# Power.net
KiCad netlist of a schematic drawn in Altium Designer
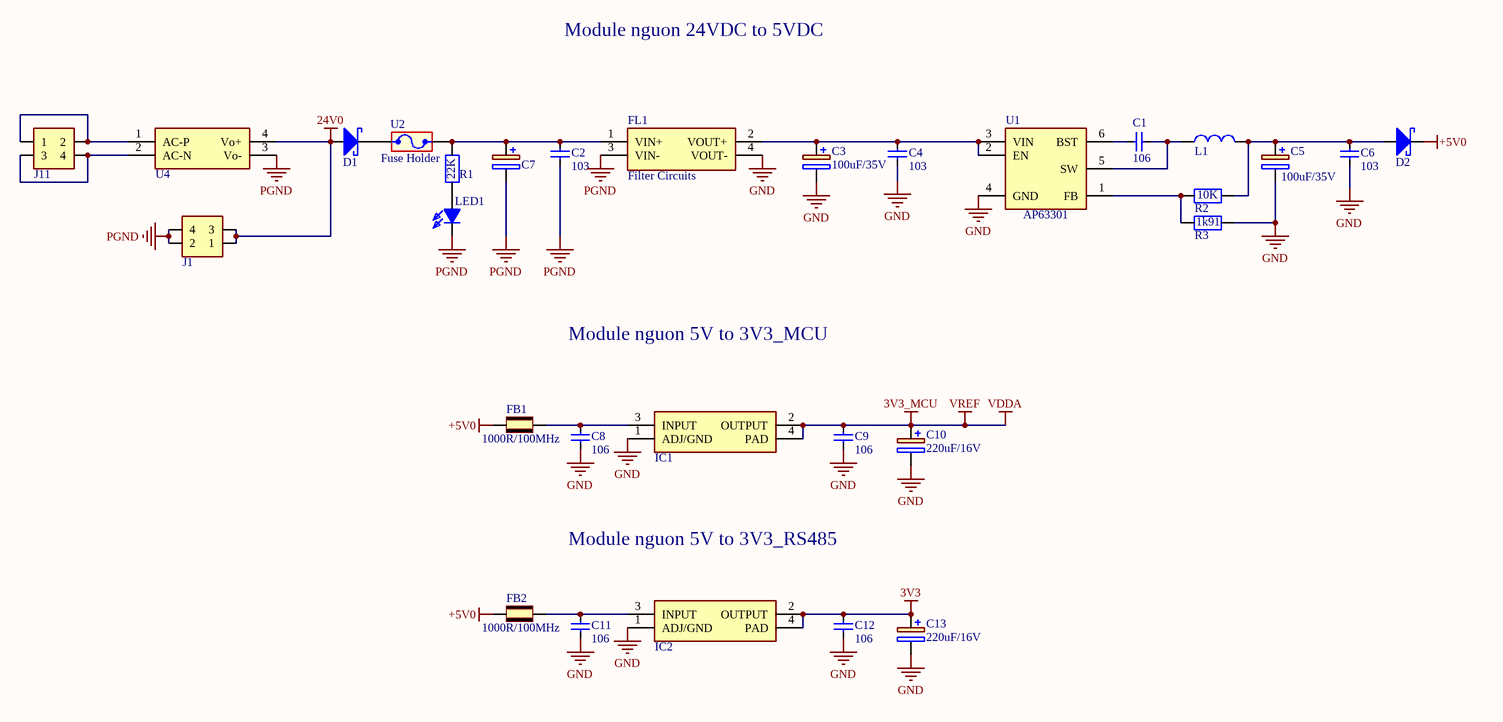
[diagram p0: Power.SchDoc]

(export (version "E")
  (design (tool "Eeschema 10.0.6"))
  (components
    (comp (ref "C1")
      (value "106")
      (footprint "SamacSys:CAPC1608X95N")
      (fields
        (field (name "MANUFACTURER_PART_NUMBER") "GRM188D71A106KA73D")
        (field (name "MOUSER PART NUMBER") "81-GRM188D71A106KA3D")
      )
      (libsource (lib "SamacSys") (part "Cap 106 - 0603"))
    )
    (comp (ref "C2")
      (value "103")
      (footprint "SamacSys:CAPC1608X95N")
      (fields
        (field (name "MANUFACTURER_PART_NUMBER") "CC0603KRX7R9BB103")
        (field (name "MOUSER PART NUMBER") "603-CC603KRX7R9BB103")
      )
      (libsource (lib "SamacSys") (part "Cap 103 - 0603"))
    )
    (comp (ref "C3")
      (value "100uF/35V")
      (footprint "SamacSys:CAPAE850X1050N")
      (description "Aluminium Electrolytic Capacitors - SMD 100UF 35V 105C 2500H")
      (fields
        (field (name "MANUFACTURER_PART_NUMBER") "MAL215097011E3")
        (field (name "MOUSER PART NUMBER") "594-MAL215097011E3")
      )
      (libsource (lib "SamacSys") (part "Cap smd 100uF/35V"))
    )
    (comp (ref "C4")
      (value "103")
      (footprint "SamacSys:CAPC1608X95N")
      (fields
        (field (name "MANUFACTURER_PART_NUMBER") "CC0603KRX7R9BB103")
        (field (name "MOUSER PART NUMBER") "603-CC603KRX7R9BB103")
      )
      (libsource (lib "SamacSys") (part "Cap 103 - 0603"))
    )
    (comp (ref "C5")
      (value "100uF/35V")
      (footprint "SamacSys:CAPAE850X1050N")
      (description "Aluminium Electrolytic Capacitors - SMD 100UF 35V 105C 2500H")
      (fields
        (field (name "MANUFACTURER_PART_NUMBER") "MAL215097011E3")
        (field (name "MOUSER PART NUMBER") "594-MAL215097011E3")
      )
      (libsource (lib "SamacSys") (part "Cap smd 100uF/35V"))
    )
    (comp (ref "C6")
      (value "103")
      (footprint "SamacSys:CAPC1608X95N")
      (fields
        (field (name "MANUFACTURER_PART_NUMBER") "CC0603KRX7R9BB103")
        (field (name "MOUSER PART NUMBER") "603-CC603KRX7R9BB103")
      )
      (libsource (lib "SamacSys") (part "Cap 103 - 0603"))
    )
    (comp (ref "C7")
      (value "330uF/35V")
      (footprint "SamacSys:CAPAE1000X1270N")
      (description "Aluminum Organic Polymer Capacitors 35Vol 330uF SMD 2KHr ESR=22 mOhms AECQ200")
      (fields
        (field (name "MANUFACTURER_PART_NUMBER") "A768MS337M1VLAS022")
        (field (name "MOUSER PART NUMBER") "80-A768MS337M1VLAS22")
      )
      (libsource (lib "SamacSys") (part "Cap smd 330uF/35V"))
    )
    (comp (ref "C8")
      (value "106")
      (footprint "SamacSys:CAPC1608X95N")
      (fields
        (field (name "MANUFACTURER_PART_NUMBER") "GRM188D71A106KA73D")
        (field (name "MOUSER PART NUMBER") "81-GRM188D71A106KA3D")
      )
      (libsource (lib "SamacSys") (part "Cap 106 - 0603"))
    )
    (comp (ref "C9")
      (value "106")
      (footprint "SamacSys:CAPC1608X95N")
      (fields
        (field (name "MANUFACTURER_PART_NUMBER") "GRM188D71A106KA73D")
        (field (name "MOUSER PART NUMBER") "81-GRM188D71A106KA3D")
      )
      (libsource (lib "SamacSys") (part "Cap 106 - 0603"))
    )
    (comp (ref "C10")
      (value "220uF/16V")
      (footprint "SamacSys:CAPPM7344X430N")
      (description "Tantalum Capacitors - Solid SMD 16V 220uF 10% 2917 Multi-anode")
      (fields
        (field (name "MANUFACTURER_PART_NUMBER") "TPME227K016R0025")
        (field (name "MOUSER PART NUMBER") "581-TPME227K016R0025")
      )
      (libsource (lib "SamacSys") (part "Cap smd 220uF/16V"))
    )
    (comp (ref "C11")
      (value "106")
      (footprint "SamacSys:CAPC1608X95N")
      (fields
        (field (name "MANUFACTURER_PART_NUMBER") "GRM188D71A106KA73D")
        (field (name "MOUSER PART NUMBER") "81-GRM188D71A106KA3D")
      )
      (libsource (lib "SamacSys") (part "Cap 106 - 0603"))
    )
    (comp (ref "C12")
      (value "106")
      (footprint "SamacSys:CAPC1608X95N")
      (fields
        (field (name "MANUFACTURER_PART_NUMBER") "GRM188D71A106KA73D")
        (field (name "MOUSER PART NUMBER") "81-GRM188D71A106KA3D")
      )
      (libsource (lib "SamacSys") (part "Cap 106 - 0603"))
    )
    (comp (ref "C13")
      (value "220uF/16V")
      (footprint "SamacSys:CAPPM7344X430N")
      (description "Tantalum Capacitors - Solid SMD 16V 220uF 10% 2917 Multi-anode")
      (fields
        (field (name "MANUFACTURER_PART_NUMBER") "TPME227K016R0025")
        (field (name "MOUSER PART NUMBER") "581-TPME227K016R0025")
      )
      (libsource (lib "SamacSys") (part "Cap smd 220uF/16V"))
    )
    (comp (ref "D1")
      (value "40V/5A")
      (footprint "SamacSys:SODFL3517X110N")
      (description "DIODE SCHOTTKY 40V 5A SMA")
      (fields
        (field (name "MANUFACTURER_PART_NUMBER") "PMEG40T30ERX")
        (field (name "MOUSER PART NUMBER") "771-PMEG40T30ERX")
      )
      (libsource (lib "SamacSys") (part "Diode 40V/5A"))
    )
    (comp (ref "D2")
      (value "40V/5A")
      (footprint "SamacSys:SODFL3517X110N")
      (description "DIODE SCHOTTKY 40V 5A SMA")
      (fields
        (field (name "MANUFACTURER_PART_NUMBER") "PMEG40T30ERX")
        (field (name "MOUSER PART NUMBER") "771-PMEG40T30ERX")
      )
      (libsource (lib "SamacSys") (part "Diode 40V/5A"))
    )
    (comp (ref "FB1")
      (value "1000R/100MHz")
      (footprint "SamacSys:BEADC2012X110N")
      (description "Ferrite Beads 1000ohms 100MHz 1A Monolithic 0805 SMD")
      (fields (field (name "MANUFACTURER_PART_NUMBER") "MI0805J102R-10"))
      (libsource (lib "SamacSys") (part "Ferrite Bead 1000R 100MHz"))
    )
    (comp (ref "FB2")
      (value "1000R/100MHz")
      (footprint "SamacSys:BEADC2012X110N")
      (description "Ferrite Beads 1000ohms 100MHz 1A Monolithic 0805 SMD")
      (fields (field (name "MANUFACTURER_PART_NUMBER") "MI0805J102R-10"))
      (libsource (lib "SamacSys") (part "Ferrite Bead 1000R 100MHz"))
    )
    (comp (ref "FL1")
      (value "Filter Circuits")
      (footprint "BNX024H01K")
      (description "EMI Filter Circuits 10.0 UF 50V 20A")
      (fields
        (field (name "MANUFACTURER_PART_NUMBER") "BNX026H01L")
        (field (name "MOUSER PART NUMBER") "81-BNX026H01L")
      )
      (libsource (lib "SamacSys") (part "Filter"))
    )
    (comp (ref "IC1")
      (value "3V3-1A")
      (footprint "SamacSys:SOT230P700X180-4N")
      (description "LDO Voltage Regulators 800MA LDO LINEAR REG A 926-LM1117IMP3.3NOPB")
      (fields (field (name "MANUFACTURER_PART_NUMBER") "LM1117IMPX3.3/NOPB"))
      (libsource (lib "SamacSys") (part "AMS1117-3V3"))
    )
    (comp (ref "IC2")
      (value "3V3-1A")
      (footprint "SamacSys:SOT230P700X180-4N")
      (description "LDO Voltage Regulators 800MA LDO LINEAR REG A 926-LM1117IMP3.3NOPB")
      (fields (field (name "MANUFACTURER_PART_NUMBER") "LM1117IMPX3.3/NOPB"))
      (libsource (lib "SamacSys") (part "AMS1117-3V3"))
    )
    (comp (ref "J1")
      (value "Connector THD 4 position 0.165\" (4.20mm)")
      (footprint "SamacSys:RHDR4W125P550X420_2X2_960X960X1310P")
      (description "Connector Header Through Hole 4 position 0.165\" (4.20mm)")
      (fields (field (name "MANUFACTURER_PART_NUMBER") "0039281043"))
      (libsource (lib "") (part "Connector 2x2_1"))
    )
    (comp (ref "J11")
      (value "Connector THD 4 position 0.165\" (4.20mm)")
      (footprint "SamacSys:RHDR4W125P550X420_2X2_960X960X1310P")
      (description "Connector Header Through Hole 4 position 0.165\" (4.20mm)")
      (fields (field (name "MANUFACTURER_PART_NUMBER") "0039281043"))
      (libsource (lib "SamacSys") (part "Connector 2x2"))
    )
    (comp (ref "L1")
      (value "Inductor 4.7uH/2A")
      (footprint "SamacSys:WE-PD2_453255")
      (description "Power Inductors - SMD WE-PD2 4532 4.7uH 1.82A .11Ohm")
      (fields
        (field (name "MANUFACTURER_PART_NUMBER") "744773047")
        (field (name "MOUSER PART NUMBER") "710-744773047")
      )
      (libsource (lib "SamacSys") (part "Inductor 4.7uH/2A"))
    )
    (comp (ref "LED1")
      (value "LED0603_BLUE")
      (footprint "SamacSys:LEDC1608X80N")
      (description "LED")
      (fields
        (field (name "MANUFACTURER_PART_NUMBER") "150060BS75000")
        (field (name "MOUSER PART NUMBER") "710-150060BS75000")
      )
      (libsource (lib "SamacSys") (part "LED0603_BLUE"))
    )
    (comp (ref "R1")
      (value "22k")
      (footprint "SamacSys:RESC1608X55N")
      (description "Thick Film Resistors - SMD 22 kOhms 100mW 0603 1%")
      (fields
        (field (name "MANUFACTURER_PART_NUMBER") "ERJ-UP3J223V")
        (field (name "MOUSER PART NUMBER") "667-ERJ-UP3J223V")
      )
      (libsource (lib "SamacSys") (part "Res 0603 22k"))
    )
    (comp (ref "R2")
      (value "10k")
      (footprint "SamacSys:RESC1608X55N")
      (description "Resistor 10 kOhms ±1% 0.1W, 1/10W Chip Resistor 0603 (1608 Metric) Automotive AEC-Q200 Thick Film")
      (fields
        (field (name "MANUFACTURER_PART_NUMBER") "ERJ-3EKF1002V")
        (field (name "MOUSER PART NUMBER") "667-ERJ-3EKF1002V")
      )
      (libsource (lib "SamacSys") (part "Res 0603 10k"))
    )
    (comp (ref "R3")
      (value "Res 0603 1k91")
      (footprint "SamacSys:RESC1608X55N")
      (description "Thick Film Resistors - SMD 1.91K 1% 1/10W")
      (fields
        (field (name "MANUFACTURER_PART_NUMBER") "CR0603-FX-1911ELF")
        (field (name "MOUSER PART NUMBER") "652-CR0603FX-1911ELF")
      )
      (libsource (lib "SamacSys") (part "Res 0603 1k91"))
    )
    (comp (ref "U1")
      (value "AP63301")
      (footprint "SamacSys:SOT95P280X100-6N")
      (description "Switching Voltage Regulators DCDC Conv HV Buck TSOT26 T&R 3K")
      (fields
        (field (name "MANUFACTURER_PART_NUMBER") "AP63301WU-7")
        (field (name "MOUSER PART NUMBER") "621-AP63301WU-7")
      )
      (libsource (lib "SamacSys") (part "AP63301"))
    )
    (comp (ref "U2")
      (value "Fuse Holder")
      (footprint "SamacSys:01550900M")
      (description "Fuse Holder ACS NANO HLDR")
      (fields
        (field (name "MANUFACTURER_PART_NUMBER") "01550900M")
        (field (name "MOUSER PART NUMBER") "576-01550900M")
      )
      (libsource (lib "SamacSys") (part "Fuse Holder"))
    )
    (comp (ref "U4")
      (value "AC/DC CONVERTER 24V 20W")
      (footprint "HLK-20M24")
      (libsource (lib "SamacSys") (part "HLK-20M24"))
    )
  )
  (nets
    (net (code "1") (name "+5V0") (class "Default")
      (node (ref "D2") (pin "1") (pinfunction "K_1") (pintype "passive"))
      (node (ref "FB1") (pin "1") (pinfunction "1_1") (pintype "passive"))
      (node (ref "FB2") (pin "1") (pinfunction "1_1") (pintype "passive"))
    )
    (net (code "2") (name "3V3") (class "Default")
      (node (ref "C12") (pin "2") (pinfunction "2_2") (pintype "passive"))
      (node (ref "C13") (pin "1") (pinfunction "+_1") (pintype "passive"))
      (node (ref "IC2") (pin "2") (pinfunction "OUTPUT_2") (pintype "passive"))
      (node (ref "IC2") (pin "4") (pinfunction "PAD_4") (pintype "passive"))
    )
    (net (code "3") (name "3V3_MCU") (class "Default")
      (node (ref "C10") (pin "1") (pinfunction "+_1") (pintype "passive"))
      (node (ref "C9") (pin "2") (pinfunction "2_2") (pintype "passive"))
      (node (ref "IC1") (pin "2") (pinfunction "OUTPUT_2") (pintype "passive"))
      (node (ref "IC1") (pin "4") (pinfunction "PAD_4") (pintype "passive"))
    )
    (net (code "4") (name "24V0") (class "Default")
      (node (ref "D1") (pin "2") (pinfunction "A_2") (pintype "passive"))
      (node (ref "J1") (pin "1") (pinfunction "1_1") (pintype "passive"))
      (node (ref "J1") (pin "3") (pinfunction "3_3") (pintype "passive"))
      (node (ref "U4") (pin "4") (pinfunction "Vo+_4") (pintype "passive"))
    )
    (net (code "5") (name "GND") (class "Default")
      (node (ref "C10") (pin "2") (pinfunction "-_2") (pintype "passive"))
      (node (ref "C11") (pin "1") (pinfunction "1_1") (pintype "passive"))
      (node (ref "C12") (pin "1") (pinfunction "1_1") (pintype "passive"))
      (node (ref "C13") (pin "2") (pinfunction "-_2") (pintype "passive"))
      (node (ref "C3") (pin "2") (pinfunction "-_2") (pintype "passive"))
      (node (ref "C4") (pin "1") (pinfunction "1_1") (pintype "passive"))
      (node (ref "C5") (pin "2") (pinfunction "-_2") (pintype "passive"))
      (node (ref "C6") (pin "1") (pinfunction "1_1") (pintype "passive"))
      (node (ref "C8") (pin "1") (pinfunction "1_1") (pintype "passive"))
      (node (ref "C9") (pin "1") (pinfunction "1_1") (pintype "passive"))
      (node (ref "FL1") (pin "4") (pinfunction "VOUT-_4") (pintype "passive"))
      (node (ref "IC1") (pin "1") (pinfunction "ADJ/GND_1") (pintype "passive"))
      (node (ref "IC2") (pin "1") (pinfunction "ADJ/GND_1") (pintype "passive"))
      (node (ref "R3") (pin "2") (pinfunction "2_2") (pintype "passive"))
      (node (ref "U1") (pin "4") (pinfunction "GND_4") (pintype "passive"))
    )
    (net (code "6") (name "Net-(C3-+)") (class "Default")
      (node (ref "C3") (pin "1") (pinfunction "+_1") (pintype "passive"))
      (node (ref "C4") (pin "2") (pinfunction "2_2") (pintype "passive"))
      (node (ref "FL1") (pin "2") (pinfunction "VOUT+_2") (pintype "passive"))
      (node (ref "U1") (pin "2") (pinfunction "EN_2") (pintype "passive"))
      (node (ref "U1") (pin "3") (pinfunction "VIN_3") (pintype "passive"))
    )
    (net (code "7") (name "Net-(C5-+)") (class "Default")
      (node (ref "C5") (pin "1") (pinfunction "+_1") (pintype "passive"))
      (node (ref "C6") (pin "2") (pinfunction "2_2") (pintype "passive"))
      (node (ref "D2") (pin "2") (pinfunction "A_2") (pintype "passive"))
      (node (ref "L1") (pin "2") (pinfunction "2_2") (pintype "passive"))
      (node (ref "R2") (pin "2") (pinfunction "2_2") (pintype "passive"))
    )
    (net (code "8") (name "Net-(C7-+)") (class "Default")
      (node (ref "C2") (pin "2") (pinfunction "2_2") (pintype "passive"))
      (node (ref "C7") (pin "1") (pinfunction "+_1") (pintype "passive"))
      (node (ref "FL1") (pin "1") (pinfunction "VIN+_1") (pintype "passive"))
      (node (ref "R1") (pin "2") (pinfunction "2_2") (pintype "passive"))
      (node (ref "U2") (pin "2") (pinfunction "2_2") (pintype "passive"))
    )
    (net (code "9") (name "Net-(D1-K)") (class "Default")
      (node (ref "D1") (pin "1") (pinfunction "K_1") (pintype "passive"))
      (node (ref "U2") (pin "1") (pinfunction "1_1") (pintype "passive"))
    )
    (net (code "10") (name "Net-(IC1-INPUT)") (class "Default")
      (node (ref "C8") (pin "2") (pinfunction "2_2") (pintype "passive"))
      (node (ref "FB1") (pin "2") (pinfunction "2_2") (pintype "passive"))
      (node (ref "IC1") (pin "3") (pinfunction "INPUT_3") (pintype "passive"))
    )
    (net (code "11") (name "Net-(IC2-INPUT)") (class "Default")
      (node (ref "C11") (pin "2") (pinfunction "2_2") (pintype "passive"))
      (node (ref "FB2") (pin "2") (pinfunction "2_2") (pintype "passive"))
      (node (ref "IC2") (pin "3") (pinfunction "INPUT_3") (pintype "passive"))
    )
    (net (code "12") (name "Net-(LED1-A)") (class "Default")
      (node (ref "LED1") (pin "2") (pinfunction "A_2") (pintype "passive"))
      (node (ref "R1") (pin "1") (pinfunction "1_1") (pintype "passive"))
    )
    (net (code "13") (name "Net-(U1-BST)") (class "Default")
      (node (ref "C1") (pin "1") (pinfunction "1_1") (pintype "passive"))
      (node (ref "U1") (pin "6") (pinfunction "BST_6") (pintype "passive"))
    )
    (net (code "14") (name "Net-(U1-FB)") (class "Default")
      (node (ref "R2") (pin "1") (pinfunction "1_1") (pintype "passive"))
      (node (ref "R3") (pin "1") (pinfunction "1_1") (pintype "passive"))
      (node (ref "U1") (pin "1") (pinfunction "FB_1") (pintype "passive"))
    )
    (net (code "15") (name "Net-(U1-SW)") (class "Default")
      (node (ref "C1") (pin "2") (pinfunction "2_2") (pintype "passive"))
      (node (ref "L1") (pin "1") (pinfunction "1_1") (pintype "passive"))
      (node (ref "U1") (pin "5") (pinfunction "SW_5") (pintype "passive"))
    )
    (net (code "16") (name "Net-(U4-AC-N)") (class "Default")
      (node (ref "J11") (pin "3") (pinfunction "3_3") (pintype "passive"))
      (node (ref "J11") (pin "4") (pinfunction "4_4") (pintype "passive"))
      (node (ref "U4") (pin "2") (pinfunction "AC-N_2") (pintype "passive"))
    )
    (net (code "17") (name "Net-(U4-AC-P)") (class "Default")
      (node (ref "J11") (pin "1") (pinfunction "1_1") (pintype "passive"))
      (node (ref "J11") (pin "2") (pinfunction "2_2") (pintype "passive"))
      (node (ref "U4") (pin "1") (pinfunction "AC-P_1") (pintype "passive"))
    )
    (net (code "18") (name "PGND") (class "Default")
      (node (ref "C2") (pin "1") (pinfunction "1_1") (pintype "passive"))
      (node (ref "C7") (pin "2") (pinfunction "-_2") (pintype "passive"))
      (node (ref "FL1") (pin "3") (pinfunction "VIN-_3") (pintype "passive"))
      (node (ref "J1") (pin "2") (pinfunction "2_2") (pintype "passive"))
      (node (ref "J1") (pin "4") (pinfunction "4_4") (pintype "passive"))
      (node (ref "LED1") (pin "1") (pinfunction "K_1") (pintype "passive"))
      (node (ref "U4") (pin "3") (pinfunction "Vo-_3") (pintype "passive"))
    )
  )
)
